# TRV_MRF49_U_V1_0_F.net
KiCad netlist of a schematic drawn in EAGLE
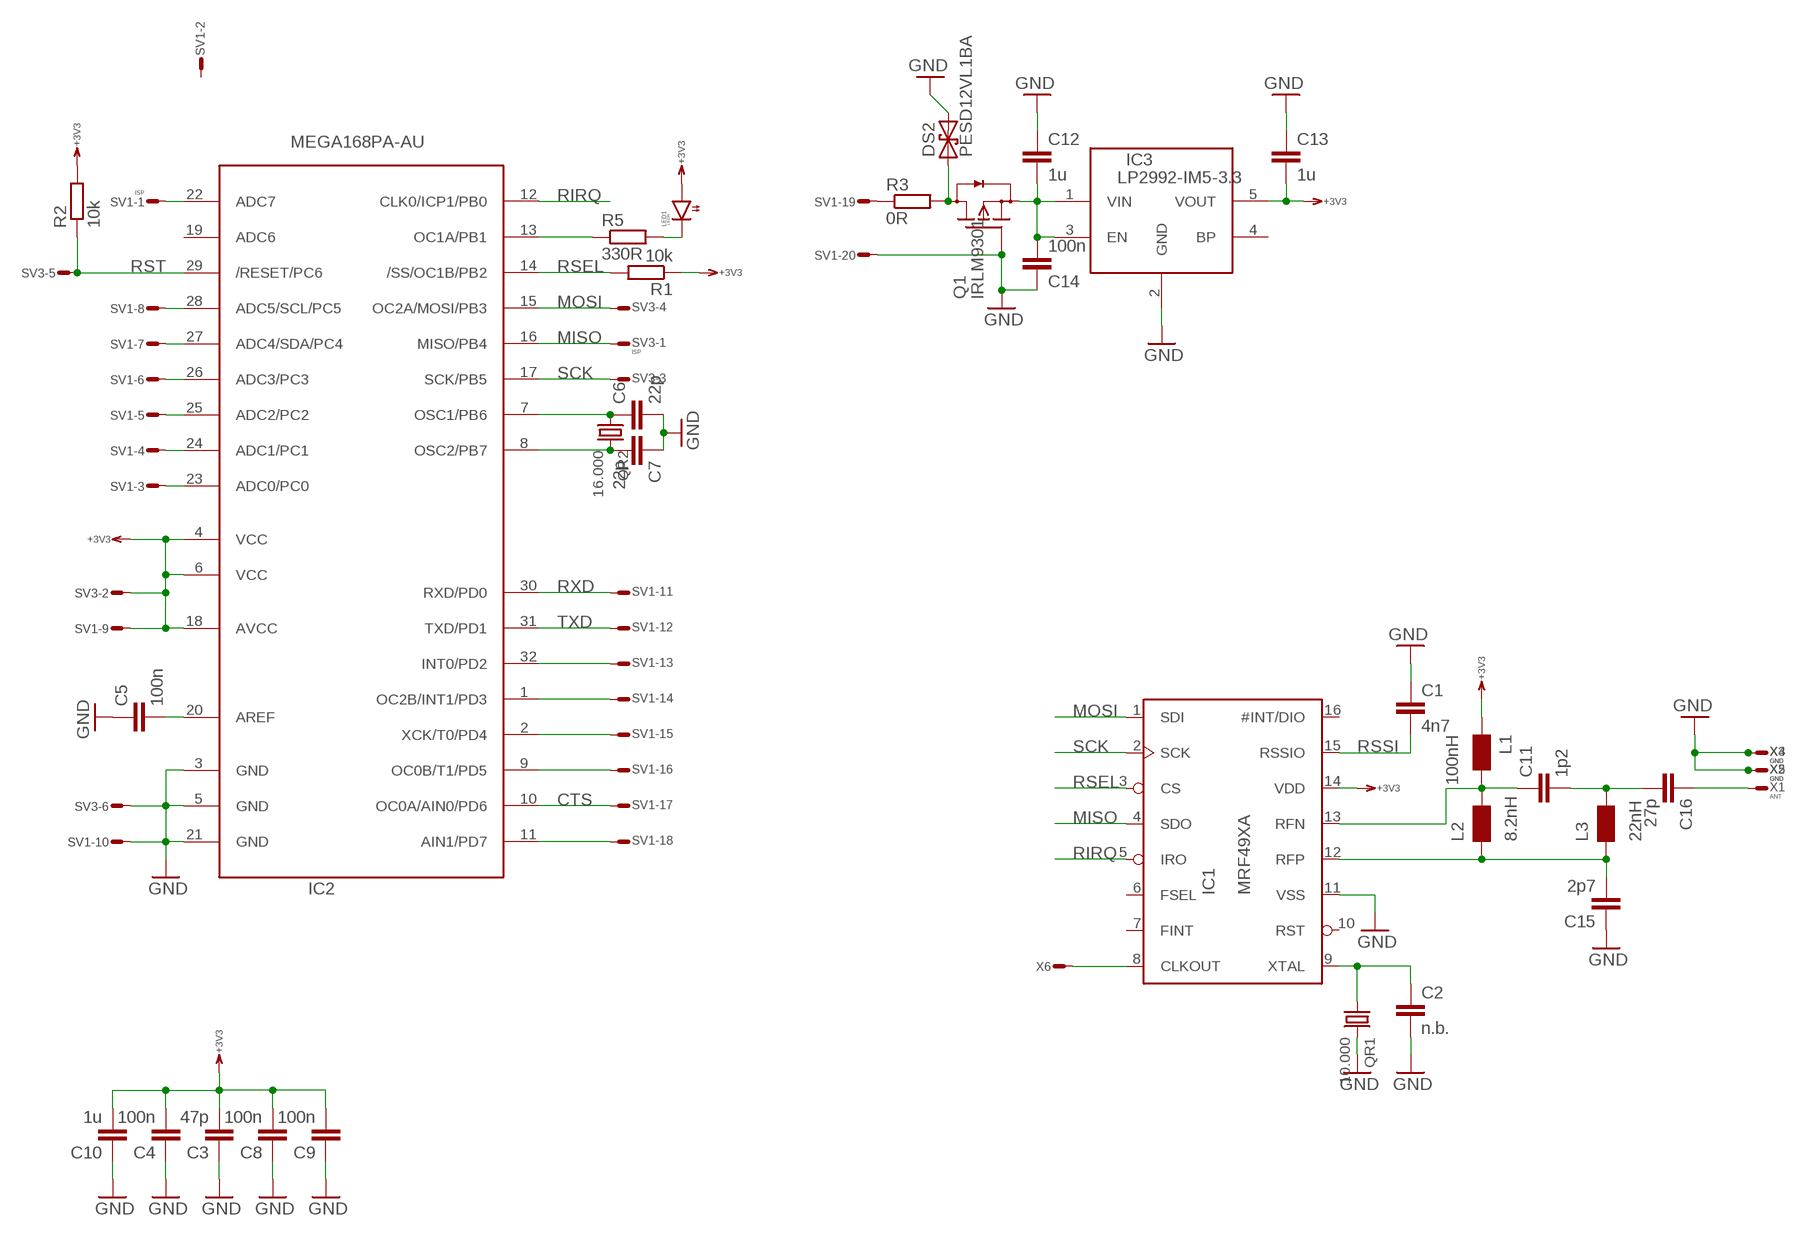
[diagram p0: schematic, sheet 1]

(export (version "E")
  (design (tool "Eeschema 10.0.6"))
  (components
    (comp (ref "C1")
      (value "4n7")
      (footprint "eagle-import:0603")
      (libsource (lib "eagle-import") (part "C0603"))
    )
    (comp (ref "C2")
      (value "n.b.")
      (footprint "eagle-import:0603")
      (libsource (lib "eagle-import") (part "C0603"))
    )
    (comp (ref "C3")
      (value "47p")
      (footprint "eagle-import:0603")
      (libsource (lib "eagle-import") (part "C0603"))
    )
    (comp (ref "C4")
      (value "100n")
      (footprint "eagle-import:0603")
      (libsource (lib "eagle-import") (part "C0603"))
    )
    (comp (ref "C5")
      (value "100n")
      (footprint "eagle-import:0603")
      (libsource (lib "eagle-import") (part "C0603"))
    )
    (comp (ref "C6")
      (value "22p")
      (footprint "eagle-import:0603")
      (libsource (lib "eagle-import") (part "C0603"))
    )
    (comp (ref "C7")
      (value "22p")
      (footprint "eagle-import:0603")
      (libsource (lib "eagle-import") (part "C0603"))
    )
    (comp (ref "C8")
      (value "100n")
      (footprint "eagle-import:0603")
      (libsource (lib "eagle-import") (part "C0603"))
    )
    (comp (ref "C9")
      (value "100n")
      (footprint "eagle-import:0603")
      (libsource (lib "eagle-import") (part "C0603"))
    )
    (comp (ref "C10")
      (value "1u")
      (footprint "eagle-import:0603")
      (libsource (lib "eagle-import") (part "C0603"))
    )
    (comp (ref "C11")
      (value "1p2")
      (footprint "eagle-import:0603")
      (libsource (lib "eagle-import") (part "C0603"))
    )
    (comp (ref "C12")
      (value "1u")
      (footprint "eagle-import:0603")
      (libsource (lib "eagle-import") (part "C0603"))
    )
    (comp (ref "C13")
      (value "1u")
      (footprint "eagle-import:0603")
      (libsource (lib "eagle-import") (part "C0603"))
    )
    (comp (ref "C14")
      (value "100n")
      (footprint "eagle-import:0603")
      (libsource (lib "eagle-import") (part "C0603"))
    )
    (comp (ref "C15")
      (value "2p7")
      (footprint "eagle-import:0603")
      (libsource (lib "eagle-import") (part "C0603"))
    )
    (comp (ref "C16")
      (value "27p")
      (footprint "eagle-import:0603")
      (libsource (lib "eagle-import") (part "C0603"))
    )
    (comp (ref "DS2")
      (value "PESD12VL1BA")
      (footprint "eagle-import:SOD323")
      (libsource (lib "eagle-import") (part "TVS-U323"))
    )
    (comp (ref "IC1")
      (value "MRF49XA")
      (footprint "eagle-import:TSSOP16")
      (libsource (lib "eagle-import") (part "MRF49XA"))
    )
    (comp (ref "IC2")
      (value "MEGA168PA-AU")
      (footprint "eagle-import:TQFP32-08")
      (libsource (lib "eagle-import") (part "MEGA168PA"))
    )
    (comp (ref "IC3")
      (value "LP2992-IM5-3.3")
      (footprint "eagle-import:SOT23-5")
      (libsource (lib "eagle-import") (part "LDO"))
    )
    (comp (ref "L1")
      (value "100nH")
      (footprint "eagle-import:0603")
      (libsource (lib "eagle-import") (part "L0603"))
    )
    (comp (ref "L2")
      (value "8.2nH")
      (footprint "eagle-import:0603")
      (libsource (lib "eagle-import") (part "L0603"))
    )
    (comp (ref "L3")
      (value "22nH")
      (footprint "eagle-import:0603")
      (libsource (lib "eagle-import") (part "L0603"))
    )
    (comp (ref "LED1")
      (value "LEDR")
      (footprint "eagle-import:0603")
      (libsource (lib "eagle-import") (part "LED0603"))
    )
    (comp (ref "Q1")
      (value "IRLM9301")
      (footprint "eagle-import:SOT23")
      (libsource (lib "eagle-import") (part "FET-PDSOT23"))
    )
    (comp (ref "QR1")
      (value "10.000")
      (footprint "eagle-import:HC49U-V")
      (libsource (lib "eagle-import") (part "Q49UV"))
    )
    (comp (ref "QR2")
      (value "16.000")
      (footprint "eagle-import:HC49U-V")
      (libsource (lib "eagle-import") (part "Q49UV"))
    )
    (comp (ref "R1")
      (value "10k")
      (footprint "eagle-import:0603")
      (libsource (lib "eagle-import") (part "R0603"))
    )
    (comp (ref "R2")
      (value "10k")
      (footprint "eagle-import:0603")
      (libsource (lib "eagle-import") (part "R0603"))
    )
    (comp (ref "R3")
      (value "0R")
      (footprint "eagle-import:0603")
      (libsource (lib "eagle-import") (part "R0603"))
    )
    (comp (ref "R5")
      (value "330R")
      (footprint "eagle-import:0603")
      (libsource (lib "eagle-import") (part "R0603"))
    )
    (comp (ref "SV1")
      (value "ISP")
      (footprint "eagle-import:ML20")
      (libsource (lib "eagle-import") (part "ML20?E"))
    )
    (comp (ref "SV3")
      (value "ISP")
      (footprint "eagle-import:ML6")
      (libsource (lib "eagle-import") (part "ML6E"))
    )
    (comp (ref "X1")
      (value "ANT")
      (footprint "eagle-import:S2.54_1.27")
      (libsource (lib "eagle-import") (part "WIREPADS2.54/1.27"))
    )
    (comp (ref "X2")
      (value "GND")
      (footprint "eagle-import:S2.54_1.27")
      (libsource (lib "eagle-import") (part "WIREPADS2.54/1.27"))
    )
    (comp (ref "X3")
      (value "GND")
      (footprint "eagle-import:S2.54_1.27")
      (libsource (lib "eagle-import") (part "WIREPADS2.54/1.27"))
    )
    (comp (ref "X4")
      (value "GND")
      (footprint "eagle-import:S2.54_1.27")
      (libsource (lib "eagle-import") (part "WIREPADS2.54/1.27"))
    )
    (comp (ref "X5")
      (value "GND")
      (footprint "eagle-import:S2.54_1.27")
      (libsource (lib "eagle-import") (part "WIREPADS2.54/1.27"))
    )
    (comp (ref "X6")
      (value "WIREPADR")
      (footprint "eagle-import:S1.27R")
      (libsource (lib "eagle-import") (part "WIREPADR"))
    )
  )
  (nets
    (net (code "1") (name "+3V3") (class "Default")
      (node (ref "C10") (pin "2") (pinfunction "2_2") (pintype "passive"))
      (node (ref "C13") (pin "2") (pinfunction "2_2") (pintype "passive"))
      (node (ref "C3") (pin "2") (pinfunction "2_2") (pintype "passive"))
      (node (ref "C4") (pin "2") (pinfunction "2_2") (pintype "passive"))
      (node (ref "C8") (pin "2") (pinfunction "2_2") (pintype "passive"))
      (node (ref "C9") (pin "2") (pinfunction "2_2") (pintype "passive"))
      (node (ref "IC1") (pin "14") (pinfunction "VDD_14") (pintype "input"))
      (node (ref "IC2") (pin "18") (pinfunction "AVCC_18") (pintype "bidirectional"))
      (node (ref "IC2") (pin "4") (pinfunction "VCC_4") (pintype "bidirectional"))
      (node (ref "IC2") (pin "6") (pinfunction "VCC_6") (pintype "bidirectional"))
      (node (ref "IC3") (pin "5") (pinfunction "VOUT_5") (pintype "bidirectional"))
      (node (ref "L1") (pin "1") (pinfunction "1_1") (pintype "passive"))
      (node (ref "LED1") (pin "1") (pinfunction "A_1") (pintype "bidirectional"))
      (node (ref "R1") (pin "1") (pinfunction "1_1") (pintype "passive"))
      (node (ref "R2") (pin "2") (pinfunction "2_2") (pintype "passive"))
      (node (ref "SV1") (pin "9") (pinfunction "S_9") (pintype "passive"))
      (node (ref "SV3") (pin "2") (pinfunction "S_2") (pintype "passive"))
    )
    (net (code "2") (name "/CTS") (class "Default")
      (node (ref "IC2") (pin "10") (pinfunction "OC0A/AIN0/PD6_10") (pintype "bidirectional"))
      (node (ref "SV1") (pin "17") (pinfunction "S_17") (pintype "passive"))
    )
    (net (code "3") (name "/MISO") (class "Default")
      (node (ref "IC1") (pin "4") (pinfunction "SDO_4") (pintype "output"))
      (node (ref "IC2") (pin "16") (pinfunction "MISO/PB4_16") (pintype "bidirectional"))
      (node (ref "SV3") (pin "1") (pinfunction "S_1") (pintype "passive"))
    )
    (net (code "4") (name "/MOSI") (class "Default")
      (node (ref "IC1") (pin "1") (pinfunction "SDI_1") (pintype "input"))
      (node (ref "IC2") (pin "15") (pinfunction "OC2A/MOSI/PB3_15") (pintype "bidirectional"))
      (node (ref "SV3") (pin "4") (pinfunction "S_4") (pintype "passive"))
    )
    (net (code "5") (name "/RIRQ") (class "Default")
      (node (ref "IC1") (pin "5") (pinfunction "IRO_5") (pintype "output"))
      (node (ref "IC2") (pin "12") (pinfunction "CLK0/ICP1/PB0_12") (pintype "bidirectional"))
    )
    (net (code "6") (name "/RSEL") (class "Default")
      (node (ref "IC1") (pin "3") (pinfunction "CS_3") (pintype "input"))
      (node (ref "IC2") (pin "14") (pinfunction "/SS/OC1B/PB2_14") (pintype "bidirectional"))
      (node (ref "R1") (pin "2") (pinfunction "2_2") (pintype "passive"))
    )
    (net (code "7") (name "/RSSI") (class "Default")
      (node (ref "C1") (pin "2") (pinfunction "2_2") (pintype "passive"))
      (node (ref "IC1") (pin "15") (pinfunction "RSSIO_15") (pintype "bidirectional"))
    )
    (net (code "8") (name "/RST") (class "Default")
      (node (ref "IC2") (pin "29") (pinfunction "/RESET/PC6_29") (pintype "bidirectional"))
      (node (ref "R2") (pin "1") (pinfunction "1_1") (pintype "passive"))
      (node (ref "SV3") (pin "5") (pinfunction "S_5") (pintype "passive"))
    )
    (net (code "9") (name "/RXD") (class "Default")
      (node (ref "IC2") (pin "30") (pinfunction "RXD/PD0_30") (pintype "bidirectional"))
      (node (ref "SV1") (pin "11") (pinfunction "S_11") (pintype "passive"))
    )
    (net (code "10") (name "/SCK") (class "Default")
      (node (ref "IC1") (pin "2") (pinfunction "SCK_2") (pintype "input"))
      (node (ref "IC2") (pin "17") (pinfunction "SCK/PB5_17") (pintype "bidirectional"))
      (node (ref "SV3") (pin "3") (pinfunction "S_3") (pintype "passive"))
    )
    (net (code "11") (name "/TXD") (class "Default")
      (node (ref "IC2") (pin "31") (pinfunction "TXD/PD1_31") (pintype "bidirectional"))
      (node (ref "SV1") (pin "12") (pinfunction "S_12") (pintype "passive"))
    )
    (net (code "12") (name "GND") (class "Default")
      (node (ref "C1") (pin "1") (pinfunction "1_1") (pintype "passive"))
      (node (ref "C10") (pin "1") (pinfunction "1_1") (pintype "passive"))
      (node (ref "C12") (pin "1") (pinfunction "1_1") (pintype "passive"))
      (node (ref "C13") (pin "1") (pinfunction "1_1") (pintype "passive"))
      (node (ref "C14") (pin "1") (pinfunction "1_1") (pintype "passive"))
      (node (ref "C15") (pin "1") (pinfunction "1_1") (pintype "passive"))
      (node (ref "C2") (pin "2") (pinfunction "2_2") (pintype "passive"))
      (node (ref "C3") (pin "1") (pinfunction "1_1") (pintype "passive"))
      (node (ref "C4") (pin "1") (pinfunction "1_1") (pintype "passive"))
      (node (ref "C5") (pin "1") (pinfunction "1_1") (pintype "passive"))
      (node (ref "C6") (pin "2") (pinfunction "2_2") (pintype "passive"))
      (node (ref "C7") (pin "1") (pinfunction "1_1") (pintype "passive"))
      (node (ref "C8") (pin "1") (pinfunction "1_1") (pintype "passive"))
      (node (ref "C9") (pin "1") (pinfunction "1_1") (pintype "passive"))
      (node (ref "DS2") (pin "C") (pinfunction "2_C") (pintype "passive"))
      (node (ref "IC1") (pin "11") (pinfunction "VSS_11") (pintype "input"))
      (node (ref "IC2") (pin "21") (pinfunction "GND_21") (pintype "bidirectional"))
      (node (ref "IC2") (pin "3") (pinfunction "GND_3") (pintype "bidirectional"))
      (node (ref "IC2") (pin "5") (pinfunction "GND_5") (pintype "bidirectional"))
      (node (ref "IC3") (pin "2") (pinfunction "GND_2") (pintype "bidirectional"))
      (node (ref "Q1") (pin "1") (pinfunction "G_1") (pintype "passive"))
      (node (ref "QR1") (pin "2") (pinfunction "2_2") (pintype "passive"))
      (node (ref "SV1") (pin "10") (pinfunction "S_10") (pintype "passive"))
      (node (ref "SV1") (pin "20") (pinfunction "S_20") (pintype "passive"))
      (node (ref "SV3") (pin "6") (pinfunction "S_6") (pintype "passive"))
      (node (ref "X2") (pin "1") (pinfunction "S_1") (pintype "passive"))
      (node (ref "X3") (pin "1") (pinfunction "S_1") (pintype "passive"))
      (node (ref "X4") (pin "1") (pinfunction "S_1") (pintype "passive"))
      (node (ref "X5") (pin "1") (pinfunction "S_1") (pintype "passive"))
    )
    (net (code "13") (name "Net-(C11-Pad2)") (class "Default")
      (node (ref "C11") (pin "2") (pinfunction "2_2") (pintype "passive"))
      (node (ref "C16") (pin "2") (pinfunction "2_2") (pintype "passive"))
      (node (ref "L3") (pin "2") (pinfunction "2_2") (pintype "passive"))
    )
    (net (code "14") (name "Net-(DS2-1)") (class "Default")
      (node (ref "DS2") (pin "A") (pinfunction "1_A") (pintype "passive"))
      (node (ref "Q1") (pin "3") (pinfunction "D_3") (pintype "passive"))
      (node (ref "R3") (pin "2") (pinfunction "2_2") (pintype "passive"))
    )
    (net (code "15") (name "Net-(IC1-CLKOUT)") (class "Default")
      (node (ref "IC1") (pin "8") (pinfunction "CLKOUT_8") (pintype "output"))
      (node (ref "X6") (pin "1") (pinfunction "S_1") (pintype "passive"))
    )
    (net (code "16") (name "Net-(IC1-RFN)") (class "Default")
      (node (ref "C11") (pin "1") (pinfunction "1_1") (pintype "passive"))
      (node (ref "IC1") (pin "13") (pinfunction "RFN_13") (pintype "bidirectional"))
      (node (ref "L1") (pin "2") (pinfunction "2_2") (pintype "passive"))
      (node (ref "L2") (pin "2") (pinfunction "2_2") (pintype "passive"))
    )
    (net (code "17") (name "Net-(IC1-RFP)") (class "Default")
      (node (ref "C15") (pin "2") (pinfunction "2_2") (pintype "passive"))
      (node (ref "IC1") (pin "12") (pinfunction "RFP_12") (pintype "bidirectional"))
      (node (ref "L2") (pin "1") (pinfunction "1_1") (pintype "passive"))
      (node (ref "L3") (pin "1") (pinfunction "1_1") (pintype "passive"))
    )
    (net (code "18") (name "Net-(IC1-XTAL)") (class "Default")
      (node (ref "C2") (pin "1") (pinfunction "1_1") (pintype "passive"))
      (node (ref "IC1") (pin "9") (pinfunction "XTAL_9") (pintype "input"))
      (node (ref "QR1") (pin "1") (pinfunction "1_1") (pintype "passive"))
    )
    (net (code "19") (name "Net-(IC2-ADC0{slash}PC0)") (class "Default")
      (node (ref "IC2") (pin "23") (pinfunction "ADC0/PC0_23") (pintype "bidirectional"))
      (node (ref "SV1") (pin "3") (pinfunction "S_3") (pintype "passive"))
    )
    (net (code "20") (name "Net-(IC2-ADC1{slash}PC1)") (class "Default")
      (node (ref "IC2") (pin "24") (pinfunction "ADC1/PC1_24") (pintype "bidirectional"))
      (node (ref "SV1") (pin "4") (pinfunction "S_4") (pintype "passive"))
    )
    (net (code "21") (name "Net-(IC2-ADC2{slash}PC2)") (class "Default")
      (node (ref "IC2") (pin "25") (pinfunction "ADC2/PC2_25") (pintype "bidirectional"))
      (node (ref "SV1") (pin "5") (pinfunction "S_5") (pintype "passive"))
    )
    (net (code "22") (name "Net-(IC2-ADC3{slash}PC3)") (class "Default")
      (node (ref "IC2") (pin "26") (pinfunction "ADC3/PC3_26") (pintype "bidirectional"))
      (node (ref "SV1") (pin "6") (pinfunction "S_6") (pintype "passive"))
    )
    (net (code "23") (name "Net-(IC2-ADC4{slash}SDA{slash}PC4)") (class "Default")
      (node (ref "IC2") (pin "27") (pinfunction "ADC4/SDA/PC4_27") (pintype "bidirectional"))
      (node (ref "SV1") (pin "7") (pinfunction "S_7") (pintype "passive"))
    )
    (net (code "24") (name "Net-(IC2-ADC5{slash}SCL{slash}PC5)") (class "Default")
      (node (ref "IC2") (pin "28") (pinfunction "ADC5/SCL/PC5_28") (pintype "bidirectional"))
      (node (ref "SV1") (pin "8") (pinfunction "S_8") (pintype "passive"))
    )
    (net (code "25") (name "Net-(IC2-ADC7)") (class "Default")
      (node (ref "IC2") (pin "22") (pinfunction "ADC7_22") (pintype "bidirectional"))
      (node (ref "SV1") (pin "1") (pinfunction "S_1") (pintype "passive"))
    )
    (net (code "26") (name "Net-(IC2-AIN1{slash}PD7)") (class "Default")
      (node (ref "IC2") (pin "11") (pinfunction "AIN1/PD7_11") (pintype "bidirectional"))
      (node (ref "SV1") (pin "18") (pinfunction "S_18") (pintype "passive"))
    )
    (net (code "27") (name "Net-(IC2-AREF)") (class "Default")
      (node (ref "C5") (pin "2") (pinfunction "2_2") (pintype "passive"))
      (node (ref "IC2") (pin "20") (pinfunction "AREF_20") (pintype "bidirectional"))
    )
    (net (code "28") (name "Net-(IC2-INT0{slash}PD2)") (class "Default")
      (node (ref "IC2") (pin "32") (pinfunction "INT0/PD2_32") (pintype "bidirectional"))
      (node (ref "SV1") (pin "13") (pinfunction "S_13") (pintype "passive"))
    )
    (net (code "29") (name "Net-(IC2-OC0B{slash}T1{slash}PD5)") (class "Default")
      (node (ref "IC2") (pin "9") (pinfunction "OC0B/T1/PD5_9") (pintype "bidirectional"))
      (node (ref "SV1") (pin "16") (pinfunction "S_16") (pintype "passive"))
    )
    (net (code "30") (name "Net-(IC2-OC1A{slash}PB1)") (class "Default")
      (node (ref "IC2") (pin "13") (pinfunction "OC1A/PB1_13") (pintype "bidirectional"))
      (node (ref "R5") (pin "1") (pinfunction "1_1") (pintype "passive"))
    )
    (net (code "31") (name "Net-(IC2-OC2B{slash}INT1{slash}PD3)") (class "Default")
      (node (ref "IC2") (pin "1") (pinfunction "OC2B/INT1/PD3_1") (pintype "bidirectional"))
      (node (ref "SV1") (pin "14") (pinfunction "S_14") (pintype "passive"))
    )
    (net (code "32") (name "Net-(IC2-OSC1{slash}PB6)") (class "Default")
      (node (ref "C6") (pin "1") (pinfunction "1_1") (pintype "passive"))
      (node (ref "IC2") (pin "7") (pinfunction "OSC1/PB6_7") (pintype "bidirectional"))
      (node (ref "QR2") (pin "1") (pinfunction "1_1") (pintype "passive"))
    )
    (net (code "33") (name "Net-(IC2-OSC2{slash}PB7)") (class "Default")
      (node (ref "C7") (pin "2") (pinfunction "2_2") (pintype "passive"))
      (node (ref "IC2") (pin "8") (pinfunction "OSC2/PB7_8") (pintype "bidirectional"))
      (node (ref "QR2") (pin "2") (pinfunction "2_2") (pintype "passive"))
    )
    (net (code "34") (name "Net-(IC2-XCK{slash}T0{slash}PD4)") (class "Default")
      (node (ref "IC2") (pin "2") (pinfunction "XCK/T0/PD4_2") (pintype "bidirectional"))
      (node (ref "SV1") (pin "15") (pinfunction "S_15") (pintype "passive"))
    )
    (net (code "35") (name "Net-(IC3-EN)") (class "Default")
      (node (ref "C12") (pin "2") (pinfunction "2_2") (pintype "passive"))
      (node (ref "C14") (pin "2") (pinfunction "2_2") (pintype "passive"))
      (node (ref "IC3") (pin "1") (pinfunction "VIN_1") (pintype "bidirectional"))
      (node (ref "IC3") (pin "3") (pinfunction "EN_3") (pintype "bidirectional"))
      (node (ref "Q1") (pin "2") (pinfunction "S_2") (pintype "passive"))
    )
    (net (code "36") (name "Net-(LED1-C)") (class "Default")
      (node (ref "LED1") (pin "2") (pinfunction "C_2") (pintype "bidirectional"))
      (node (ref "R5") (pin "2") (pinfunction "2_2") (pintype "passive"))
    )
    (net (code "37") (name "Net-(SV1K-S)") (class "Default")
      (node (ref "R3") (pin "1") (pinfunction "1_1") (pintype "passive"))
      (node (ref "SV1") (pin "19") (pinfunction "S_19") (pintype "passive"))
    )
    (net (code "38") (name "Net-(X1-S)") (class "Default")
      (node (ref "C16") (pin "1") (pinfunction "1_1") (pintype "passive"))
      (node (ref "X1") (pin "1") (pinfunction "S_1") (pintype "passive"))
    )
    (net (code "39") (name "unconnected-(IC1-#INT{slash}DIO-Pad16)") (class "Default")
      (node (ref "IC1") (pin "16") (pinfunction "#INT/DIO_16") (pintype "bidirectional"))
    )
    (net (code "40") (name "unconnected-(IC1-FINT-Pad7)") (class "Default")
      (node (ref "IC1") (pin "7") (pinfunction "FINT_7") (pintype "bidirectional"))
    )
    (net (code "41") (name "unconnected-(IC1-FSEL-Pad6)") (class "Default")
      (node (ref "IC1") (pin "6") (pinfunction "FSEL_6") (pintype "bidirectional"))
    )
    (net (code "42") (name "unconnected-(IC1-RST-Pad10)") (class "Default")
      (node (ref "IC1") (pin "10") (pinfunction "RST_10") (pintype "bidirectional"))
    )
    (net (code "43") (name "unconnected-(IC2-ADC6-Pad19)") (class "Default")
      (node (ref "IC2") (pin "19") (pinfunction "ADC6_19") (pintype "bidirectional"))
    )
    (net (code "44") (name "unconnected-(IC3-BP-Pad4)") (class "Default")
      (node (ref "IC3") (pin "4") (pinfunction "BP_4") (pintype "bidirectional"))
    )
    (net (code "45") (name "unconnected-(SV1L-S-Pad2)") (class "Default")
      (node (ref "SV1") (pin "2") (pinfunction "S_2") (pintype "passive"))
    )
  )
)
